# wristwatch.net
KiCad netlist of a schematic drawn in EAGLE
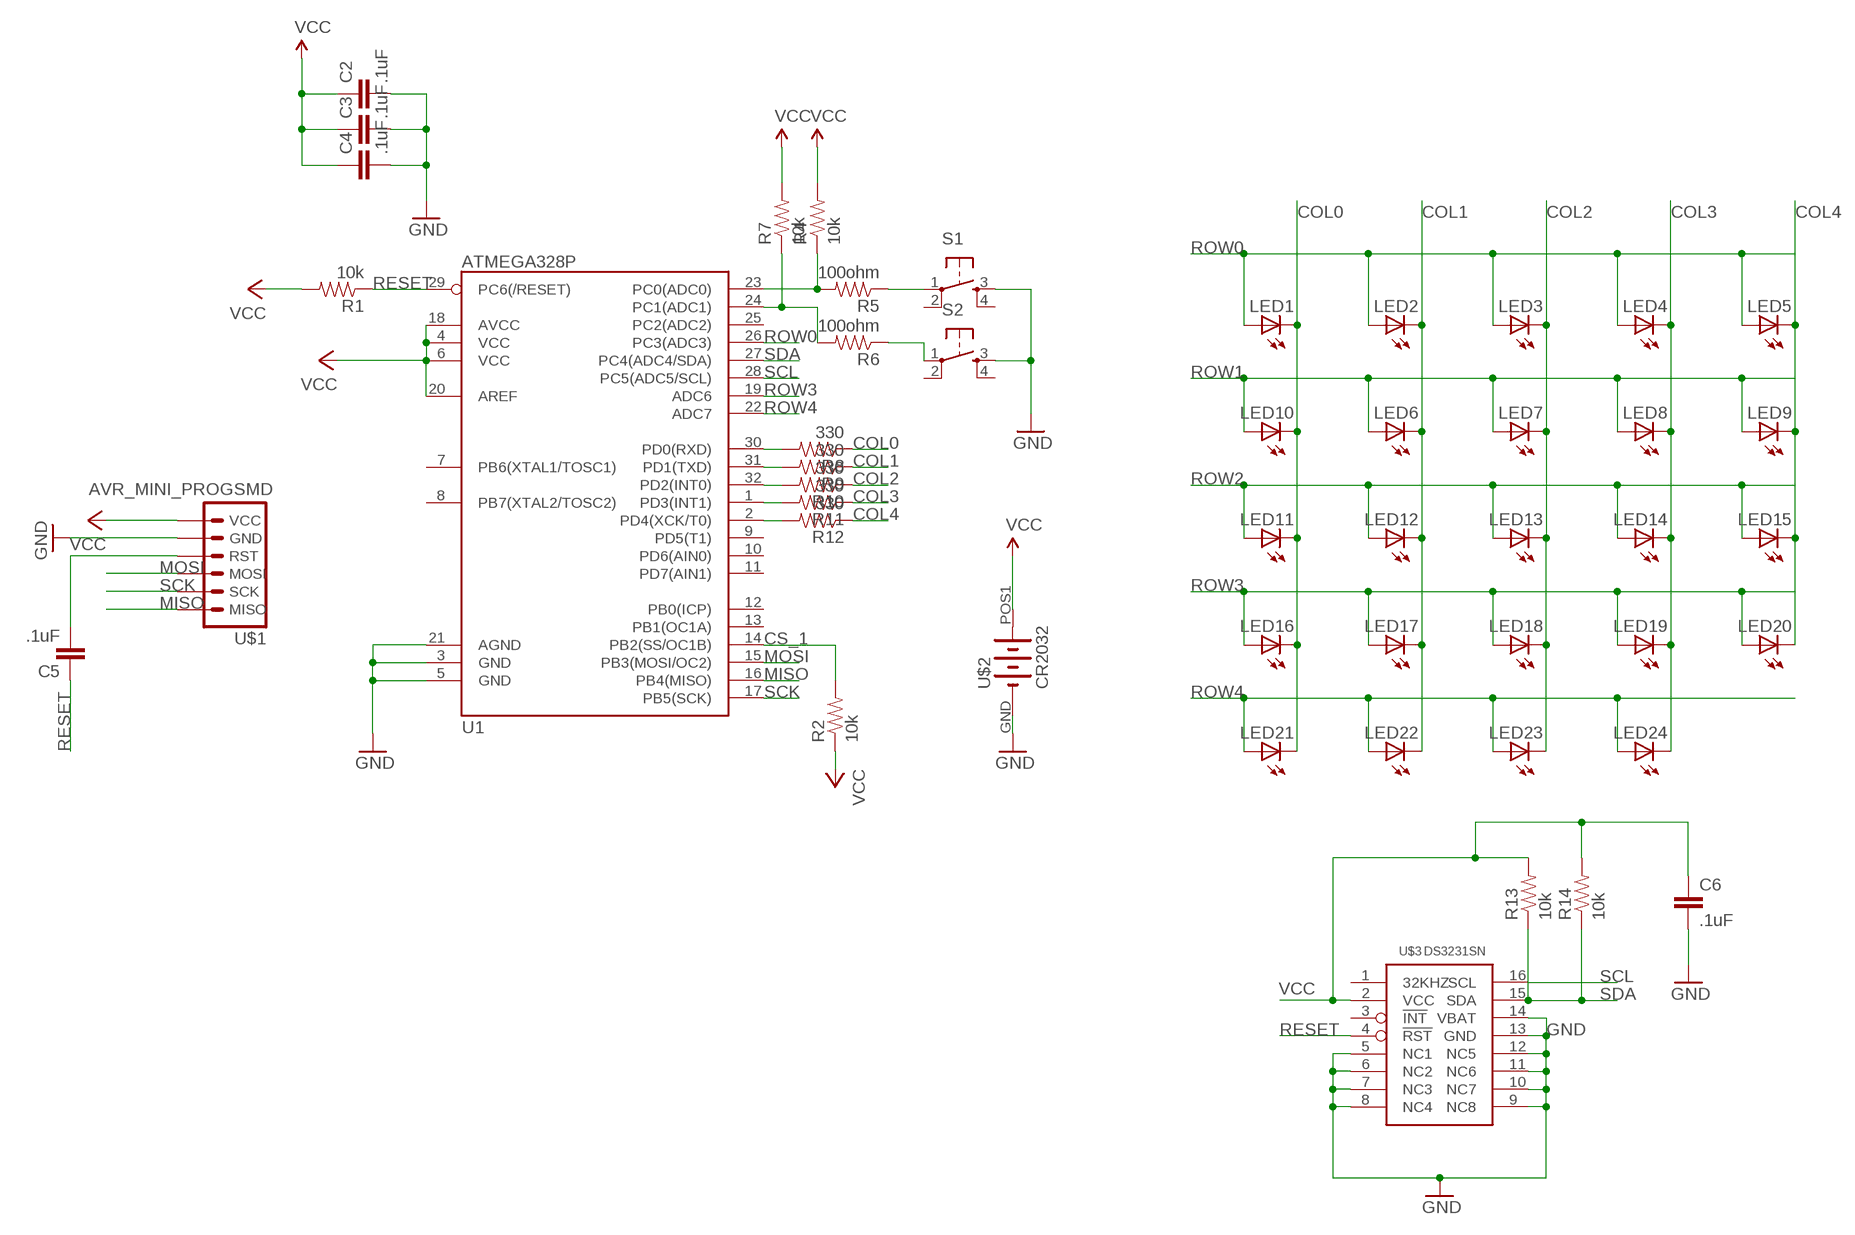
[diagram p0: schematic, sheet 1]

(export (version "E")
  (design (tool "Eeschema 10.0.6"))
  (components
    (comp (ref "C2")
      (value ".1uF")
      (footprint "eagle-import:0805")
      (libsource (lib "eagle-import") (part "CAP0805"))
    )
    (comp (ref "C3")
      (value ".1uF")
      (footprint "eagle-import:0805")
      (libsource (lib "eagle-import") (part "CAP0805"))
    )
    (comp (ref "C4")
      (value ".1uF")
      (footprint "eagle-import:0805")
      (libsource (lib "eagle-import") (part "CAP0805"))
    )
    (comp (ref "C5")
      (value ".1uF")
      (footprint "eagle-import:0805")
      (libsource (lib "eagle-import") (part "CAP0805"))
    )
    (comp (ref "C6")
      (value ".1uF")
      (footprint "eagle-import:0805")
      (libsource (lib "eagle-import") (part "CAP0805"))
    )
    (comp (ref "LED1")
      (value "LEDCHIP-LED0805")
      (footprint "eagle-import:CHIP-LED0805")
      (libsource (lib "eagle-import") (part "LEDCHIP-LED0805"))
    )
    (comp (ref "LED2")
      (value "LEDCHIP-LED0805")
      (footprint "eagle-import:CHIP-LED0805")
      (libsource (lib "eagle-import") (part "LEDCHIP-LED0805"))
    )
    (comp (ref "LED3")
      (value "LEDCHIP-LED0805")
      (footprint "eagle-import:CHIP-LED0805")
      (libsource (lib "eagle-import") (part "LEDCHIP-LED0805"))
    )
    (comp (ref "LED4")
      (value "LEDCHIP-LED0805")
      (footprint "eagle-import:CHIP-LED0805")
      (libsource (lib "eagle-import") (part "LEDCHIP-LED0805"))
    )
    (comp (ref "LED5")
      (value "LEDCHIP-LED0805")
      (footprint "eagle-import:CHIP-LED0805")
      (libsource (lib "eagle-import") (part "LEDCHIP-LED0805"))
    )
    (comp (ref "LED6")
      (value "LEDCHIP-LED0805")
      (footprint "eagle-import:CHIP-LED0805")
      (libsource (lib "eagle-import") (part "LEDCHIP-LED0805"))
    )
    (comp (ref "LED7")
      (value "LEDCHIP-LED0805")
      (footprint "eagle-import:CHIP-LED0805")
      (libsource (lib "eagle-import") (part "LEDCHIP-LED0805"))
    )
    (comp (ref "LED8")
      (value "LEDCHIP-LED0805")
      (footprint "eagle-import:CHIP-LED0805")
      (libsource (lib "eagle-import") (part "LEDCHIP-LED0805"))
    )
    (comp (ref "LED9")
      (value "LEDCHIP-LED0805")
      (footprint "eagle-import:CHIP-LED0805")
      (libsource (lib "eagle-import") (part "LEDCHIP-LED0805"))
    )
    (comp (ref "LED10")
      (value "LEDCHIP-LED0805")
      (footprint "eagle-import:CHIP-LED0805")
      (libsource (lib "eagle-import") (part "LEDCHIP-LED0805"))
    )
    (comp (ref "LED11")
      (value "LEDCHIP-LED0805")
      (footprint "eagle-import:CHIP-LED0805")
      (libsource (lib "eagle-import") (part "LEDCHIP-LED0805"))
    )
    (comp (ref "LED12")
      (value "LEDCHIP-LED0805")
      (footprint "eagle-import:CHIP-LED0805")
      (libsource (lib "eagle-import") (part "LEDCHIP-LED0805"))
    )
    (comp (ref "LED13")
      (value "LEDCHIP-LED0805")
      (footprint "eagle-import:CHIP-LED0805")
      (libsource (lib "eagle-import") (part "LEDCHIP-LED0805"))
    )
    (comp (ref "LED14")
      (value "LEDCHIP-LED0805")
      (footprint "eagle-import:CHIP-LED0805")
      (libsource (lib "eagle-import") (part "LEDCHIP-LED0805"))
    )
    (comp (ref "LED15")
      (value "LEDCHIP-LED0805")
      (footprint "eagle-import:CHIP-LED0805")
      (libsource (lib "eagle-import") (part "LEDCHIP-LED0805"))
    )
    (comp (ref "LED16")
      (value "LEDCHIP-LED0805")
      (footprint "eagle-import:CHIP-LED0805")
      (libsource (lib "eagle-import") (part "LEDCHIP-LED0805"))
    )
    (comp (ref "LED17")
      (value "LEDCHIP-LED0805")
      (footprint "eagle-import:CHIP-LED0805")
      (libsource (lib "eagle-import") (part "LEDCHIP-LED0805"))
    )
    (comp (ref "LED18")
      (value "LEDCHIP-LED0805")
      (footprint "eagle-import:CHIP-LED0805")
      (libsource (lib "eagle-import") (part "LEDCHIP-LED0805"))
    )
    (comp (ref "LED19")
      (value "LEDCHIP-LED0805")
      (footprint "eagle-import:CHIP-LED0805")
      (libsource (lib "eagle-import") (part "LEDCHIP-LED0805"))
    )
    (comp (ref "LED20")
      (value "LEDCHIP-LED0805")
      (footprint "eagle-import:CHIP-LED0805")
      (libsource (lib "eagle-import") (part "LEDCHIP-LED0805"))
    )
    (comp (ref "LED21")
      (value "LEDCHIP-LED0805")
      (footprint "eagle-import:CHIP-LED0805")
      (libsource (lib "eagle-import") (part "LEDCHIP-LED0805"))
    )
    (comp (ref "LED22")
      (value "LEDCHIP-LED0805")
      (footprint "eagle-import:CHIP-LED0805")
      (libsource (lib "eagle-import") (part "LEDCHIP-LED0805"))
    )
    (comp (ref "LED23")
      (value "LEDCHIP-LED0805")
      (footprint "eagle-import:CHIP-LED0805")
      (libsource (lib "eagle-import") (part "LEDCHIP-LED0805"))
    )
    (comp (ref "LED24")
      (value "LEDCHIP-LED0805")
      (footprint "eagle-import:CHIP-LED0805")
      (libsource (lib "eagle-import") (part "LEDCHIP-LED0805"))
    )
    (comp (ref "R1")
      (value "10k")
      (footprint "eagle-import:SPARKFUN_0805")
      (libsource (lib "eagle-import") (part "SPARKFUN_RESISTOR0805-RES"))
    )
    (comp (ref "R2")
      (value "10k")
      (footprint "eagle-import:SPARKFUN_0805")
      (libsource (lib "eagle-import") (part "SPARKFUN_RESISTOR0805-RES"))
    )
    (comp (ref "R4")
      (value "10k")
      (footprint "eagle-import:SPARKFUN_0805")
      (libsource (lib "eagle-import") (part "SPARKFUN_RESISTOR0805-RES"))
    )
    (comp (ref "R5")
      (value "100ohm")
      (footprint "eagle-import:SPARKFUN_0805")
      (libsource (lib "eagle-import") (part "SPARKFUN_RESISTOR0805-RES"))
    )
    (comp (ref "R6")
      (value "100ohm")
      (footprint "eagle-import:SPARKFUN_0805")
      (libsource (lib "eagle-import") (part "SPARKFUN_RESISTOR0805-RES"))
    )
    (comp (ref "R7")
      (value "10k")
      (footprint "eagle-import:SPARKFUN_0805")
      (libsource (lib "eagle-import") (part "SPARKFUN_RESISTOR0805-RES"))
    )
    (comp (ref "R8")
      (value "330")
      (footprint "eagle-import:SPARKFUN_0805")
      (libsource (lib "eagle-import") (part "SPARKFUN_RESISTOR0805-RES"))
    )
    (comp (ref "R9")
      (value "330")
      (footprint "eagle-import:SPARKFUN_0805")
      (libsource (lib "eagle-import") (part "SPARKFUN_RESISTOR0805-RES"))
    )
    (comp (ref "R10")
      (value "330")
      (footprint "eagle-import:SPARKFUN_0805")
      (libsource (lib "eagle-import") (part "SPARKFUN_RESISTOR0805-RES"))
    )
    (comp (ref "R11")
      (value "330")
      (footprint "eagle-import:SPARKFUN_0805")
      (libsource (lib "eagle-import") (part "SPARKFUN_RESISTOR0805-RES"))
    )
    (comp (ref "R12")
      (value "330")
      (footprint "eagle-import:SPARKFUN_0805")
      (libsource (lib "eagle-import") (part "SPARKFUN_RESISTOR0805-RES"))
    )
    (comp (ref "R13")
      (value "10k")
      (footprint "eagle-import:SPARKFUN_0805")
      (libsource (lib "eagle-import") (part "SPARKFUN_RESISTOR0805-RES"))
    )
    (comp (ref "R14")
      (value "10k")
      (footprint "eagle-import:SPARKFUN_0805")
      (libsource (lib "eagle-import") (part "SPARKFUN_RESISTOR0805-RES"))
    )
    (comp (ref "S1")
      (value "TAC_SWITCHSMD")
      (footprint "eagle-import:TACTILE-SWITCH-SMD")
      (libsource (lib "eagle-import") (part "TAC_SWITCHSMD"))
    )
    (comp (ref "S2")
      (value "TAC_SWITCHSMD")
      (footprint "eagle-import:TACTILE-SWITCH-SMD")
      (libsource (lib "eagle-import") (part "TAC_SWITCHSMD"))
    )
    (comp (ref "U$1")
      (value "AVR_MINI_PROGSMD")
      (footprint "eagle-import:AVR_MINI_PROG")
      (libsource (lib "eagle-import") (part "AVR_MINI_PROGSMD"))
    )
    (comp (ref "U$2")
      (value "CR2032")
      (footprint "eagle-import:CR2032-BAT-HLD")
      (libsource (lib "eagle-import") (part "CR2032"))
    )
    (comp (ref "U$3")
      (value "DS3231SN")
      (footprint "eagle-import:SO16L")
      (libsource (lib "eagle-import") (part "DS3231SN"))
    )
    (comp (ref "U1")
      (value "ATMEGA328P")
      (footprint "eagle-import:TQFP32-08")
      (libsource (lib "eagle-import") (part "ATMEGA328_SMT"))
    )
  )
  (nets
    (net (code "1") (name "/COL0") (class "Default")
      (node (ref "LED1") (pin "C") (pinfunction "C_C") (pintype "passive"))
      (node (ref "LED10") (pin "C") (pinfunction "C_C") (pintype "passive"))
      (node (ref "LED11") (pin "C") (pinfunction "C_C") (pintype "passive"))
      (node (ref "LED16") (pin "C") (pinfunction "C_C") (pintype "passive"))
      (node (ref "LED21") (pin "C") (pinfunction "C_C") (pintype "passive"))
      (node (ref "R8") (pin "1") (pinfunction "1_1") (pintype "passive"))
    )
    (net (code "2") (name "/COL1") (class "Default")
      (node (ref "LED12") (pin "C") (pinfunction "C_C") (pintype "passive"))
      (node (ref "LED17") (pin "C") (pinfunction "C_C") (pintype "passive"))
      (node (ref "LED2") (pin "C") (pinfunction "C_C") (pintype "passive"))
      (node (ref "LED22") (pin "C") (pinfunction "C_C") (pintype "passive"))
      (node (ref "LED6") (pin "C") (pinfunction "C_C") (pintype "passive"))
      (node (ref "R9") (pin "1") (pinfunction "1_1") (pintype "passive"))
    )
    (net (code "3") (name "/COL2") (class "Default")
      (node (ref "LED13") (pin "C") (pinfunction "C_C") (pintype "passive"))
      (node (ref "LED18") (pin "C") (pinfunction "C_C") (pintype "passive"))
      (node (ref "LED23") (pin "C") (pinfunction "C_C") (pintype "passive"))
      (node (ref "LED3") (pin "C") (pinfunction "C_C") (pintype "passive"))
      (node (ref "LED7") (pin "C") (pinfunction "C_C") (pintype "passive"))
      (node (ref "R10") (pin "1") (pinfunction "1_1") (pintype "passive"))
    )
    (net (code "4") (name "/COL3") (class "Default")
      (node (ref "LED14") (pin "C") (pinfunction "C_C") (pintype "passive"))
      (node (ref "LED19") (pin "C") (pinfunction "C_C") (pintype "passive"))
      (node (ref "LED24") (pin "C") (pinfunction "C_C") (pintype "passive"))
      (node (ref "LED4") (pin "C") (pinfunction "C_C") (pintype "passive"))
      (node (ref "LED8") (pin "C") (pinfunction "C_C") (pintype "passive"))
      (node (ref "R11") (pin "1") (pinfunction "1_1") (pintype "passive"))
    )
    (net (code "5") (name "/COL4") (class "Default")
      (node (ref "LED15") (pin "C") (pinfunction "C_C") (pintype "passive"))
      (node (ref "LED20") (pin "C") (pinfunction "C_C") (pintype "passive"))
      (node (ref "LED5") (pin "C") (pinfunction "C_C") (pintype "passive"))
      (node (ref "LED9") (pin "C") (pinfunction "C_C") (pintype "passive"))
      (node (ref "R12") (pin "1") (pinfunction "1_1") (pintype "passive"))
    )
    (net (code "6") (name "/CS_1") (class "Default")
      (node (ref "R2") (pin "2") (pinfunction "2_2") (pintype "passive"))
      (node (ref "U1") (pin "14") (pinfunction "PB2(SS/OC1B)_14") (pintype "bidirectional"))
    )
    (net (code "7") (name "/MISO") (class "Default")
      (node (ref "U$1") (pin "6") (pinfunction "MISO_6") (pintype "passive"))
      (node (ref "U1") (pin "16") (pinfunction "PB4(MISO)_16") (pintype "bidirectional"))
    )
    (net (code "8") (name "/MOSI") (class "Default")
      (node (ref "U$1") (pin "4") (pinfunction "MOSI_4") (pintype "passive"))
      (node (ref "U1") (pin "15") (pinfunction "PB3(MOSI/OC2)_15") (pintype "bidirectional"))
    )
    (net (code "9") (name "/RESET") (class "Default")
      (node (ref "C5") (pin "1") (pinfunction "1_1") (pintype "passive"))
      (node (ref "R1") (pin "1") (pinfunction "1_1") (pintype "passive"))
      (node (ref "U$3") (pin "4") (pinfunction "~{RST}_4") (pintype "bidirectional"))
      (node (ref "U1") (pin "29") (pinfunction "PC6(/RESET)_29") (pintype "bidirectional"))
    )
    (net (code "10") (name "/ROW0") (class "Default")
      (node (ref "LED1") (pin "A") (pinfunction "A_A") (pintype "passive"))
      (node (ref "LED2") (pin "A") (pinfunction "A_A") (pintype "passive"))
      (node (ref "LED3") (pin "A") (pinfunction "A_A") (pintype "passive"))
      (node (ref "LED4") (pin "A") (pinfunction "A_A") (pintype "passive"))
      (node (ref "LED5") (pin "A") (pinfunction "A_A") (pintype "passive"))
      (node (ref "U1") (pin "26") (pinfunction "PC3(ADC3)_26") (pintype "bidirectional"))
    )
    (net (code "11") (name "/ROW1") (class "Default")
      (node (ref "LED10") (pin "A") (pinfunction "A_A") (pintype "passive"))
      (node (ref "LED6") (pin "A") (pinfunction "A_A") (pintype "passive"))
      (node (ref "LED7") (pin "A") (pinfunction "A_A") (pintype "passive"))
      (node (ref "LED8") (pin "A") (pinfunction "A_A") (pintype "passive"))
      (node (ref "LED9") (pin "A") (pinfunction "A_A") (pintype "passive"))
    )
    (net (code "12") (name "/ROW2") (class "Default")
      (node (ref "LED11") (pin "A") (pinfunction "A_A") (pintype "passive"))
      (node (ref "LED12") (pin "A") (pinfunction "A_A") (pintype "passive"))
      (node (ref "LED13") (pin "A") (pinfunction "A_A") (pintype "passive"))
      (node (ref "LED14") (pin "A") (pinfunction "A_A") (pintype "passive"))
      (node (ref "LED15") (pin "A") (pinfunction "A_A") (pintype "passive"))
    )
    (net (code "13") (name "/ROW3") (class "Default")
      (node (ref "LED16") (pin "A") (pinfunction "A_A") (pintype "passive"))
      (node (ref "LED17") (pin "A") (pinfunction "A_A") (pintype "passive"))
      (node (ref "LED18") (pin "A") (pinfunction "A_A") (pintype "passive"))
      (node (ref "LED19") (pin "A") (pinfunction "A_A") (pintype "passive"))
      (node (ref "LED20") (pin "A") (pinfunction "A_A") (pintype "passive"))
      (node (ref "U1") (pin "19") (pinfunction "ADC6_19") (pintype "bidirectional"))
    )
    (net (code "14") (name "/ROW4") (class "Default")
      (node (ref "LED21") (pin "A") (pinfunction "A_A") (pintype "passive"))
      (node (ref "LED22") (pin "A") (pinfunction "A_A") (pintype "passive"))
      (node (ref "LED23") (pin "A") (pinfunction "A_A") (pintype "passive"))
      (node (ref "LED24") (pin "A") (pinfunction "A_A") (pintype "passive"))
      (node (ref "U1") (pin "22") (pinfunction "ADC7_22") (pintype "bidirectional"))
    )
    (net (code "15") (name "/SCK") (class "Default")
      (node (ref "U$1") (pin "5") (pinfunction "SCK_5") (pintype "passive"))
      (node (ref "U1") (pin "17") (pinfunction "PB5(SCK)_17") (pintype "bidirectional"))
    )
    (net (code "16") (name "/SCL") (class "Default")
      (node (ref "U$3") (pin "16") (pinfunction "SCL_16") (pintype "bidirectional"))
      (node (ref "U1") (pin "28") (pinfunction "PC5(ADC5/SCL)_28") (pintype "bidirectional"))
    )
    (net (code "17") (name "/SDA") (class "Default")
      (node (ref "R13") (pin "1") (pinfunction "1_1") (pintype "passive"))
      (node (ref "R14") (pin "1") (pinfunction "1_1") (pintype "passive"))
      (node (ref "U$3") (pin "15") (pinfunction "SDA_15") (pintype "bidirectional"))
      (node (ref "U1") (pin "27") (pinfunction "PC4(ADC4/SDA)_27") (pintype "bidirectional"))
    )
    (net (code "18") (name "GND") (class "Default")
      (node (ref "C2") (pin "2") (pinfunction "2_2") (pintype "passive"))
      (node (ref "C3") (pin "2") (pinfunction "2_2") (pintype "passive"))
      (node (ref "C4") (pin "2") (pinfunction "2_2") (pintype "passive"))
      (node (ref "C6") (pin "2") (pinfunction "2_2") (pintype "passive"))
      (node (ref "S1") (pin "3") (pinfunction "3_3") (pintype "passive"))
      (node (ref "S2") (pin "3") (pinfunction "3_3") (pintype "passive"))
      (node (ref "U$1") (pin "2") (pinfunction "GND_2") (pintype "passive"))
      (node (ref "U$2") (pin "GND") (pinfunction "-_GND") (pintype "passive"))
      (node (ref "U$3") (pin "10") (pinfunction "NC7_10") (pintype "bidirectional"))
      (node (ref "U$3") (pin "11") (pinfunction "NC6_11") (pintype "bidirectional"))
      (node (ref "U$3") (pin "12") (pinfunction "NC5_12") (pintype "bidirectional"))
      (node (ref "U$3") (pin "13") (pinfunction "GND_13") (pintype "bidirectional"))
      (node (ref "U$3") (pin "14") (pinfunction "VBAT_14") (pintype "bidirectional"))
      (node (ref "U$3") (pin "5") (pinfunction "NC1_5") (pintype "bidirectional"))
      (node (ref "U$3") (pin "6") (pinfunction "NC2_6") (pintype "bidirectional"))
      (node (ref "U$3") (pin "7") (pinfunction "NC3_7") (pintype "bidirectional"))
      (node (ref "U$3") (pin "8") (pinfunction "NC4_8") (pintype "bidirectional"))
      (node (ref "U$3") (pin "9") (pinfunction "NC8_9") (pintype "bidirectional"))
      (node (ref "U1") (pin "21") (pinfunction "AGND_21") (pintype "bidirectional"))
      (node (ref "U1") (pin "3") (pinfunction "GND_3") (pintype "bidirectional"))
      (node (ref "U1") (pin "5") (pinfunction "GND_5") (pintype "bidirectional"))
    )
    (net (code "19") (name "Net-(R5-Pad1)") (class "Default")
      (node (ref "R5") (pin "1") (pinfunction "1_1") (pintype "passive"))
      (node (ref "S1") (pin "1") (pinfunction "1_1") (pintype "passive"))
    )
    (net (code "20") (name "Net-(R6-Pad1)") (class "Default")
      (node (ref "R6") (pin "1") (pinfunction "1_1") (pintype "passive"))
      (node (ref "S2") (pin "1") (pinfunction "1_1") (pintype "passive"))
    )
    (net (code "21") (name "Net-(U$1-RST)") (class "Default")
      (node (ref "C5") (pin "2") (pinfunction "2_2") (pintype "passive"))
      (node (ref "U$1") (pin "3") (pinfunction "RST_3") (pintype "passive"))
    )
    (net (code "22") (name "Net-(U1-PC0(ADC0))") (class "Default")
      (node (ref "R4") (pin "1") (pinfunction "1_1") (pintype "passive"))
      (node (ref "R5") (pin "2") (pinfunction "2_2") (pintype "passive"))
      (node (ref "U1") (pin "23") (pinfunction "PC0(ADC0)_23") (pintype "bidirectional"))
    )
    (net (code "23") (name "Net-(U1-PC1(ADC1))") (class "Default")
      (node (ref "R6") (pin "2") (pinfunction "2_2") (pintype "passive"))
      (node (ref "R7") (pin "1") (pinfunction "1_1") (pintype "passive"))
      (node (ref "U1") (pin "24") (pinfunction "PC1(ADC1)_24") (pintype "bidirectional"))
    )
    (net (code "24") (name "Net-(U1-PD0(RXD))") (class "Default")
      (node (ref "R8") (pin "2") (pinfunction "2_2") (pintype "passive"))
      (node (ref "U1") (pin "30") (pinfunction "PD0(RXD)_30") (pintype "bidirectional"))
    )
    (net (code "25") (name "Net-(U1-PD1(TXD))") (class "Default")
      (node (ref "R9") (pin "2") (pinfunction "2_2") (pintype "passive"))
      (node (ref "U1") (pin "31") (pinfunction "PD1(TXD)_31") (pintype "bidirectional"))
    )
    (net (code "26") (name "Net-(U1-PD2(INT0))") (class "Default")
      (node (ref "R10") (pin "2") (pinfunction "2_2") (pintype "passive"))
      (node (ref "U1") (pin "32") (pinfunction "PD2(INT0)_32") (pintype "bidirectional"))
    )
    (net (code "27") (name "Net-(U1-PD3(INT1))") (class "Default")
      (node (ref "R11") (pin "2") (pinfunction "2_2") (pintype "passive"))
      (node (ref "U1") (pin "1") (pinfunction "PD3(INT1)_1") (pintype "bidirectional"))
    )
    (net (code "28") (name "Net-(U1-PD4(XCK{slash}T0))") (class "Default")
      (node (ref "R12") (pin "2") (pinfunction "2_2") (pintype "passive"))
      (node (ref "U1") (pin "2") (pinfunction "PD4(XCK/T0)_2") (pintype "bidirectional"))
    )
    (net (code "29") (name "VCC") (class "Default")
      (node (ref "C2") (pin "1") (pinfunction "1_1") (pintype "passive"))
      (node (ref "C3") (pin "1") (pinfunction "1_1") (pintype "passive"))
      (node (ref "C4") (pin "1") (pinfunction "1_1") (pintype "passive"))
      (node (ref "C6") (pin "1") (pinfunction "1_1") (pintype "passive"))
      (node (ref "R1") (pin "2") (pinfunction "2_2") (pintype "passive"))
      (node (ref "R13") (pin "2") (pinfunction "2_2") (pintype "passive"))
      (node (ref "R14") (pin "2") (pinfunction "2_2") (pintype "passive"))
      (node (ref "R2") (pin "1") (pinfunction "1_1") (pintype "passive"))
      (node (ref "R4") (pin "2") (pinfunction "2_2") (pintype "passive"))
      (node (ref "R7") (pin "2") (pinfunction "2_2") (pintype "passive"))
      (node (ref "U$1") (pin "1") (pinfunction "VCC_1") (pintype "passive"))
      (node (ref "U$2") (pin "POS1") (pinfunction "+_POS1") (pintype "passive"))
      (node (ref "U$3") (pin "2") (pinfunction "VCC_2") (pintype "bidirectional"))
      (node (ref "U1") (pin "18") (pinfunction "AVCC_18") (pintype "bidirectional"))
      (node (ref "U1") (pin "20") (pinfunction "AREF_20") (pintype "bidirectional"))
      (node (ref "U1") (pin "4") (pinfunction "VCC_4") (pintype "bidirectional"))
      (node (ref "U1") (pin "6") (pinfunction "VCC_6") (pintype "bidirectional"))
    )
    (net (code "30") (name "unconnected-(S1-Pad2)") (class "Default")
      (node (ref "S1") (pin "2") (pinfunction "2_2") (pintype "passive"))
    )
    (net (code "31") (name "unconnected-(S1-Pad4)") (class "Default")
      (node (ref "S1") (pin "4") (pinfunction "4_4") (pintype "passive"))
    )
    (net (code "32") (name "unconnected-(S2-Pad2)") (class "Default")
      (node (ref "S2") (pin "2") (pinfunction "2_2") (pintype "passive"))
    )
    (net (code "33") (name "unconnected-(S2-Pad4)") (class "Default")
      (node (ref "S2") (pin "4") (pinfunction "4_4") (pintype "passive"))
    )
    (net (code "34") (name "unconnected-(U$2-+-PadPOS2)") (class "Default")
      (node (ref "U$2") (pin "POS2") (pinfunction "+_POS2") (pintype "passive"))
    )
    (net (code "35") (name "unconnected-(U$3-32KHZ-Pad1)") (class "Default")
      (node (ref "U$3") (pin "1") (pinfunction "32KHZ_1") (pintype "bidirectional"))
    )
    (net (code "36") (name "unconnected-(U$3-~{INT}-Pad3)") (class "Default")
      (node (ref "U$3") (pin "3") (pinfunction "~{INT}_3") (pintype "bidirectional"))
    )
    (net (code "37") (name "unconnected-(U1-PB0(ICP)-Pad12)") (class "Default")
      (node (ref "U1") (pin "12") (pinfunction "PB0(ICP)_12") (pintype "bidirectional"))
    )
    (net (code "38") (name "unconnected-(U1-PB1(OC1A)-Pad13)") (class "Default")
      (node (ref "U1") (pin "13") (pinfunction "PB1(OC1A)_13") (pintype "bidirectional"))
    )
    (net (code "39") (name "unconnected-(U1-PB6(XTAL1{slash}TOSC1)-Pad7)") (class "Default")
      (node (ref "U1") (pin "7") (pinfunction "PB6(XTAL1/TOSC1)_7") (pintype "bidirectional"))
    )
    (net (code "40") (name "unconnected-(U1-PB7(XTAL2{slash}TOSC2)-Pad8)") (class "Default")
      (node (ref "U1") (pin "8") (pinfunction "PB7(XTAL2/TOSC2)_8") (pintype "bidirectional"))
    )
    (net (code "41") (name "unconnected-(U1-PC2(ADC2)-Pad25)") (class "Default")
      (node (ref "U1") (pin "25") (pinfunction "PC2(ADC2)_25") (pintype "bidirectional"))
    )
    (net (code "42") (name "unconnected-(U1-PD5(T1)-Pad9)") (class "Default")
      (node (ref "U1") (pin "9") (pinfunction "PD5(T1)_9") (pintype "bidirectional"))
    )
    (net (code "43") (name "unconnected-(U1-PD6(AIN0)-Pad10)") (class "Default")
      (node (ref "U1") (pin "10") (pinfunction "PD6(AIN0)_10") (pintype "bidirectional"))
    )
    (net (code "44") (name "unconnected-(U1-PD7(AIN1)-Pad11)") (class "Default")
      (node (ref "U1") (pin "11") (pinfunction "PD7(AIN1)_11") (pintype "bidirectional"))
    )
  )
)
